# 8_EBUS.net
KiCad netlist of a schematic drawn in EAGLE
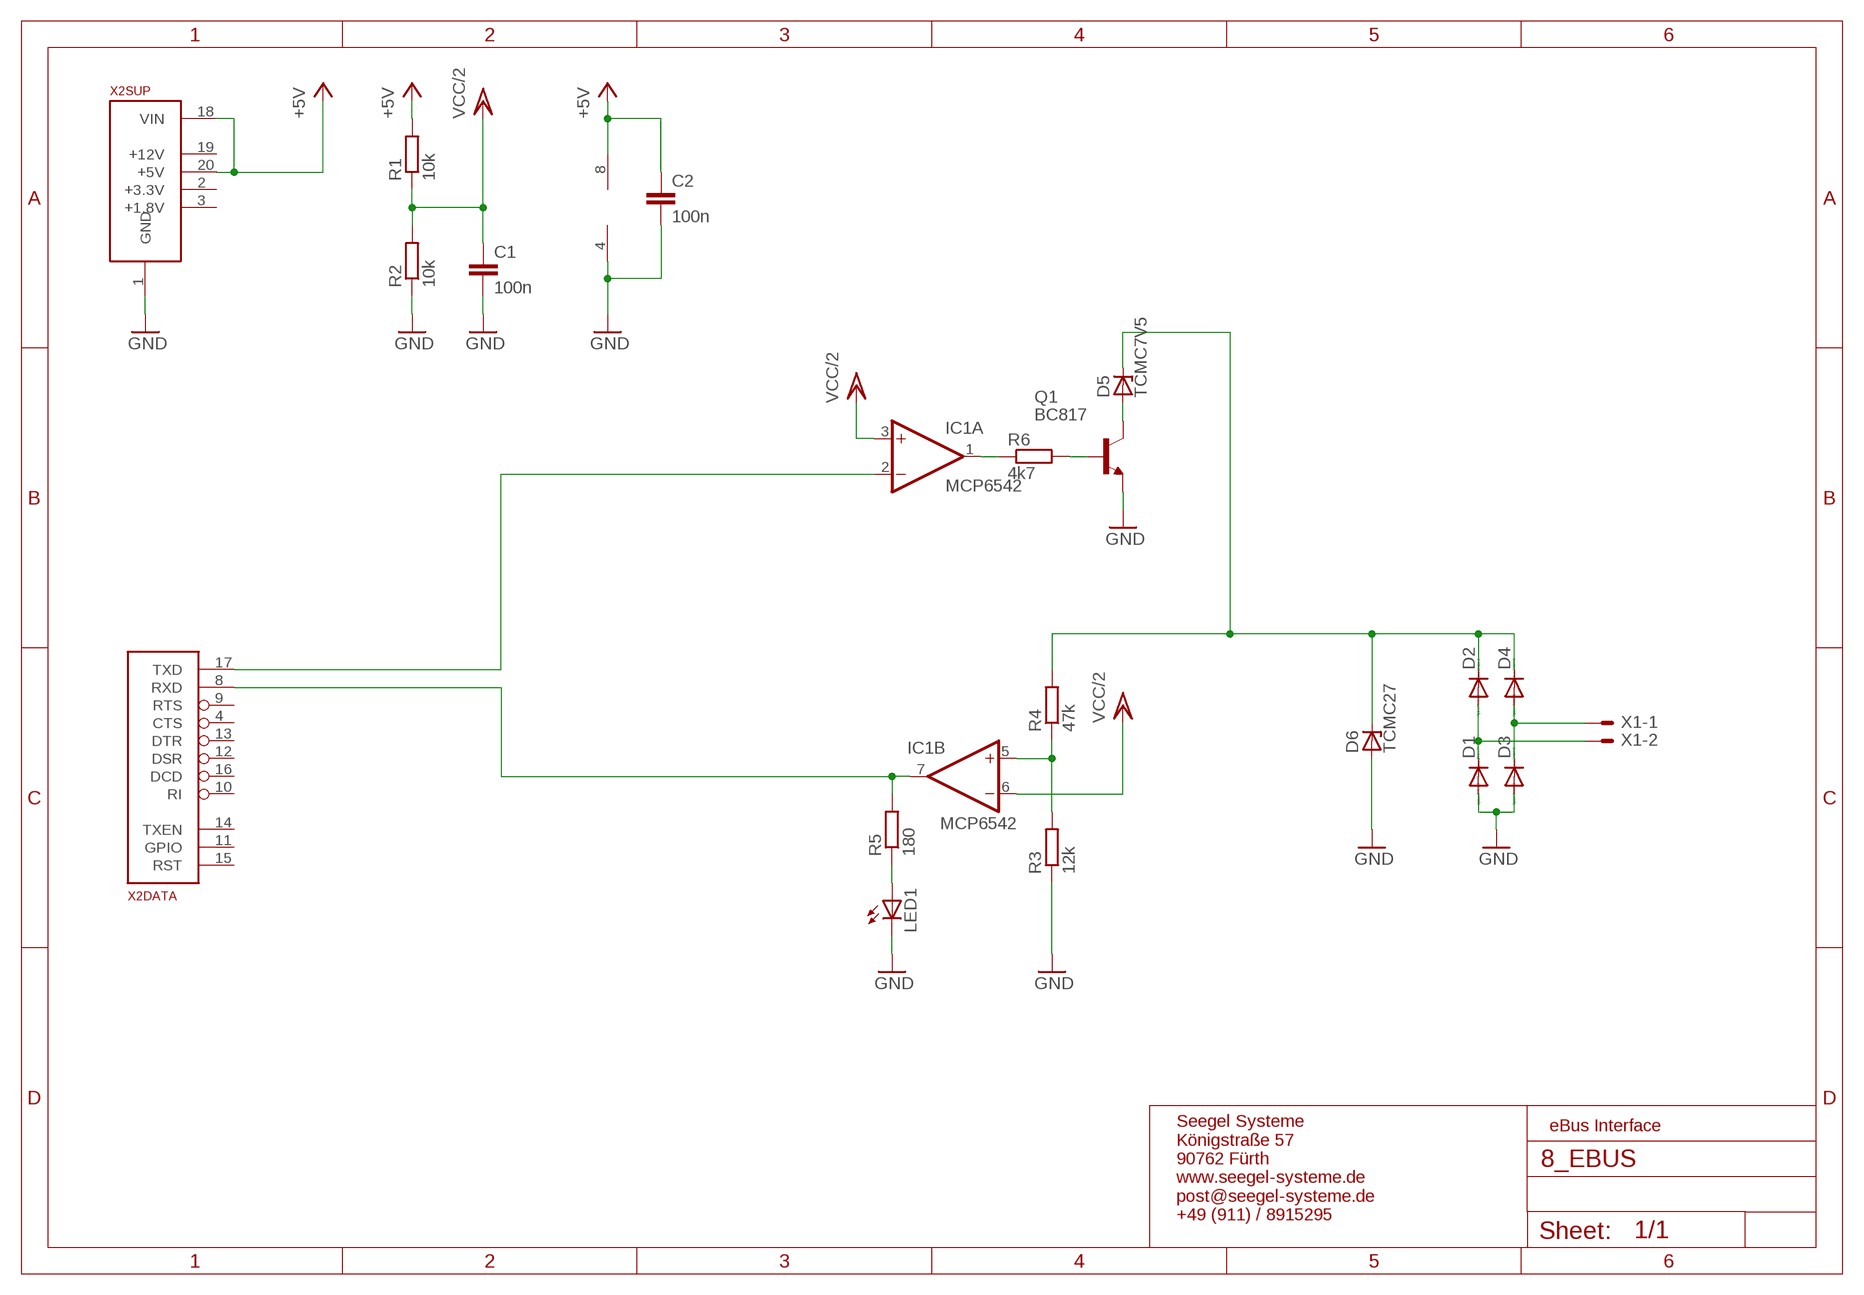
[diagram p0: schematic, sheet 1]

(export (version "E")
  (design (tool "Eeschema 10.0.6"))
  (components
    (comp (ref "C1")
      (value "100n")
      (footprint "eagle-import:C0805")
      (libsource (lib "eagle-import") (part "C-EUC0805"))
    )
    (comp (ref "C2")
      (value "100n")
      (footprint "eagle-import:C0805")
      (libsource (lib "eagle-import") (part "C-EUC0805"))
    )
    (comp (ref "D1")
      (value "DIODE-SOD80C")
      (footprint "eagle-import:SOD80C")
      (libsource (lib "eagle-import") (part "DIODE-SOD80C"))
    )
    (comp (ref "D2")
      (value "DIODE-SOD80C")
      (footprint "eagle-import:SOD80C")
      (libsource (lib "eagle-import") (part "DIODE-SOD80C"))
    )
    (comp (ref "D3")
      (value "DIODE-SOD80C")
      (footprint "eagle-import:SOD80C")
      (libsource (lib "eagle-import") (part "DIODE-SOD80C"))
    )
    (comp (ref "D4")
      (value "DIODE-SOD80C")
      (footprint "eagle-import:SOD80C")
      (libsource (lib "eagle-import") (part "DIODE-SOD80C"))
    )
    (comp (ref "D5")
      (value "TCMC7V5")
      (footprint "eagle-import:SOD80C")
      (libsource (lib "eagle-import") (part "ZENER-DIODESOD80C"))
    )
    (comp (ref "D6")
      (value "TCMC27")
      (footprint "eagle-import:SOD80C")
      (libsource (lib "eagle-import") (part "ZENER-DIODESOD80C"))
    )
    (comp (ref "IC1")
      (value "MCP6542")
      (footprint "eagle-import:SO08")
      (libsource (lib "eagle-import") (part "LM393D"))
    )
    (comp (ref "LED1")
      (value "LEDCHIPLED_0805")
      (footprint "eagle-import:CHIPLED_0805")
      (libsource (lib "eagle-import") (part "LEDCHIPLED_0805"))
    )
    (comp (ref "Q1")
      (value "BC817")
      (footprint "eagle-import:SOT23-BEC")
      (libsource (lib "eagle-import") (part "BC817SMD-16LT1"))
    )
    (comp (ref "R1")
      (value "10k")
      (footprint "eagle-import:R0805")
      (libsource (lib "eagle-import") (part "R-EU_R0805"))
    )
    (comp (ref "R2")
      (value "10k")
      (footprint "eagle-import:R0805")
      (libsource (lib "eagle-import") (part "R-EU_R0805"))
    )
    (comp (ref "R3")
      (value "12k")
      (footprint "eagle-import:R0805")
      (libsource (lib "eagle-import") (part "R-EU_R0805"))
    )
    (comp (ref "R4")
      (value "47k")
      (footprint "eagle-import:R0805")
      (libsource (lib "eagle-import") (part "R-EU_R0805"))
    )
    (comp (ref "R5")
      (value "180")
      (footprint "eagle-import:R0805")
      (libsource (lib "eagle-import") (part "R-EU_R0805"))
    )
    (comp (ref "R6")
      (value "4k7")
      (footprint "eagle-import:R0805")
      (libsource (lib "eagle-import") (part "R-EU_R0805"))
    )
    (comp (ref "X1")
      (value "AKL18X-02W")
      (footprint "eagle-import:AKL182-02")
      (libsource (lib "eagle-import") (part "AKL18X-02W"))
    )
    (comp (ref "X2")
      (value "ALLSERIALSLAVE")
      (footprint "eagle-import:DAUGHTER-THT")
      (libsource (lib "eagle-import") (part "ALLSERIALSLAVE"))
    )
  )
  (nets
    (net (code "1") (name "+5V") (class "Default")
      (node (ref "C2") (pin "1") (pinfunction "1_1") (pintype "passive"))
      (node (ref "IC1") (pin "8") (pinfunction "V+_8") (pintype "power_in"))
      (node (ref "R1") (pin "2") (pinfunction "2_2") (pintype "passive"))
      (node (ref "X2") (pin "18") (pinfunction "VIN_18") (pintype "bidirectional"))
      (node (ref "X2") (pin "20") (pinfunction "+5V_20") (pintype "bidirectional"))
    )
    (net (code "2") (name "GND") (class "Default")
      (node (ref "C1") (pin "2") (pinfunction "2_2") (pintype "passive"))
      (node (ref "C2") (pin "2") (pinfunction "2_2") (pintype "passive"))
      (node (ref "D1") (pin "A") (pinfunction "A_A") (pintype "passive"))
      (node (ref "D3") (pin "A") (pinfunction "A_A") (pintype "passive"))
      (node (ref "D6") (pin "A") (pinfunction "A_A") (pintype "passive"))
      (node (ref "IC1") (pin "4") (pinfunction "V-_4") (pintype "power_in"))
      (node (ref "LED1") (pin "C") (pinfunction "C_C") (pintype "passive"))
      (node (ref "Q1") (pin "E") (pinfunction "E_E") (pintype "passive"))
      (node (ref "R2") (pin "1") (pinfunction "1_1") (pintype "passive"))
      (node (ref "R3") (pin "1") (pinfunction "1_1") (pintype "passive"))
      (node (ref "X2") (pin "1") (pinfunction "GND_1") (pintype "bidirectional"))
    )
    (net (code "3") (name "Net-(D2-PadC)") (class "Default")
      (node (ref "D2") (pin "C") (pinfunction "C_C") (pintype "passive"))
      (node (ref "D4") (pin "C") (pinfunction "C_C") (pintype "passive"))
      (node (ref "D5") (pin "C") (pinfunction "C_C") (pintype "passive"))
      (node (ref "D6") (pin "C") (pinfunction "C_C") (pintype "passive"))
      (node (ref "R4") (pin "2") (pinfunction "2_2") (pintype "passive"))
    )
    (net (code "4") (name "Net-(D5-PadA)") (class "Default")
      (node (ref "D5") (pin "A") (pinfunction "A_A") (pintype "passive"))
      (node (ref "Q1") (pin "C") (pinfunction "C_C") (pintype "passive"))
    )
    (net (code "5") (name "Net-(IC1A--IN)") (class "Default")
      (node (ref "IC1") (pin "2") (pinfunction "-IN_2") (pintype "input"))
      (node (ref "X2") (pin "17") (pinfunction "TXD_17") (pintype "output"))
    )
    (net (code "6") (name "Net-(IC1A-OUT)") (class "Default")
      (node (ref "IC1") (pin "1") (pinfunction "OUT_1") (pintype "output"))
      (node (ref "R6") (pin "1") (pinfunction "1_1") (pintype "passive"))
    )
    (net (code "7") (name "Net-(IC1B-+IN)") (class "Default")
      (node (ref "IC1") (pin "5") (pinfunction "+IN_5") (pintype "input"))
      (node (ref "R3") (pin "2") (pinfunction "2_2") (pintype "passive"))
      (node (ref "R4") (pin "1") (pinfunction "1_1") (pintype "passive"))
    )
    (net (code "8") (name "Net-(IC1B-OUT)") (class "Default")
      (node (ref "IC1") (pin "7") (pinfunction "OUT_7") (pintype "output"))
      (node (ref "R5") (pin "2") (pinfunction "2_2") (pintype "passive"))
      (node (ref "X2") (pin "8") (pinfunction "RXD_8") (pintype "input"))
    )
    (net (code "9") (name "Net-(LED1-PadA)") (class "Default")
      (node (ref "LED1") (pin "A") (pinfunction "A_A") (pintype "passive"))
      (node (ref "R5") (pin "1") (pinfunction "1_1") (pintype "passive"))
    )
    (net (code "10") (name "Net-(Q1-PadB)") (class "Default")
      (node (ref "Q1") (pin "B") (pinfunction "B_B") (pintype "passive"))
      (node (ref "R6") (pin "2") (pinfunction "2_2") (pintype "passive"))
    )
    (net (code "11") (name "Net-(X1A-S)") (class "Default")
      (node (ref "D3") (pin "C") (pinfunction "C_C") (pintype "passive"))
      (node (ref "D4") (pin "A") (pinfunction "A_A") (pintype "passive"))
      (node (ref "X1") (pin "P$1") (pinfunction "S_P$1") (pintype "passive"))
    )
    (net (code "12") (name "Net-(X1B-S)") (class "Default")
      (node (ref "D1") (pin "C") (pinfunction "C_C") (pintype "passive"))
      (node (ref "D2") (pin "A") (pinfunction "A_A") (pintype "passive"))
      (node (ref "X1") (pin "P$2") (pinfunction "S_P$2") (pintype "passive"))
    )
    (net (code "13") (name "VCC{slash}2") (class "Default")
      (node (ref "C1") (pin "1") (pinfunction "1_1") (pintype "passive"))
      (node (ref "IC1") (pin "3") (pinfunction "+IN_3") (pintype "input"))
      (node (ref "IC1") (pin "6") (pinfunction "-IN_6") (pintype "input"))
      (node (ref "R1") (pin "1") (pinfunction "1_1") (pintype "passive"))
      (node (ref "R2") (pin "2") (pinfunction "2_2") (pintype "passive"))
    )
    (net (code "14") (name "unconnected-(X2A-CTS-Pad4)") (class "Default")
      (node (ref "X2") (pin "4") (pinfunction "CTS_4") (pintype "input"))
    )
    (net (code "15") (name "unconnected-(X2A-DCD-Pad16)") (class "Default")
      (node (ref "X2") (pin "16") (pinfunction "DCD_16") (pintype "input"))
    )
    (net (code "16") (name "unconnected-(X2A-DSR-Pad12)") (class "Default")
      (node (ref "X2") (pin "12") (pinfunction "DSR_12") (pintype "input"))
    )
    (net (code "17") (name "unconnected-(X2A-DTR-Pad13)") (class "Default")
      (node (ref "X2") (pin "13") (pinfunction "DTR_13") (pintype "output"))
    )
    (net (code "18") (name "unconnected-(X2A-GPIO-Pad11)") (class "Default")
      (node (ref "X2") (pin "11") (pinfunction "GPIO_11") (pintype "bidirectional"))
    )
    (net (code "19") (name "unconnected-(X2A-RI-Pad10)") (class "Default")
      (node (ref "X2") (pin "10") (pinfunction "RI_10") (pintype "input"))
    )
    (net (code "20") (name "unconnected-(X2A-RST-Pad15)") (class "Default")
      (node (ref "X2") (pin "15") (pinfunction "RST_15") (pintype "bidirectional"))
    )
    (net (code "21") (name "unconnected-(X2A-RTS-Pad9)") (class "Default")
      (node (ref "X2") (pin "9") (pinfunction "RTS_9") (pintype "output"))
    )
    (net (code "22") (name "unconnected-(X2A-TXEN-Pad14)") (class "Default")
      (node (ref "X2") (pin "14") (pinfunction "TXEN_14") (pintype "output"))
    )
    (net (code "23") (name "unconnected-(X2B-+1.8V-Pad3)") (class "Default")
      (node (ref "X2") (pin "3") (pinfunction "+1.8V_3") (pintype "bidirectional"))
    )
    (net (code "24") (name "unconnected-(X2B-+3.3V-Pad2)") (class "Default")
      (node (ref "X2") (pin "2") (pinfunction "+3.3V_2") (pintype "bidirectional"))
    )
    (net (code "25") (name "unconnected-(X2B-+12V-Pad19)") (class "Default")
      (node (ref "X2") (pin "19") (pinfunction "+12V_19") (pintype "bidirectional"))
    )
  )
)
